# Arduino_DUE_shield_Design.net
KiCad netlist of a schematic drawn in EAGLE
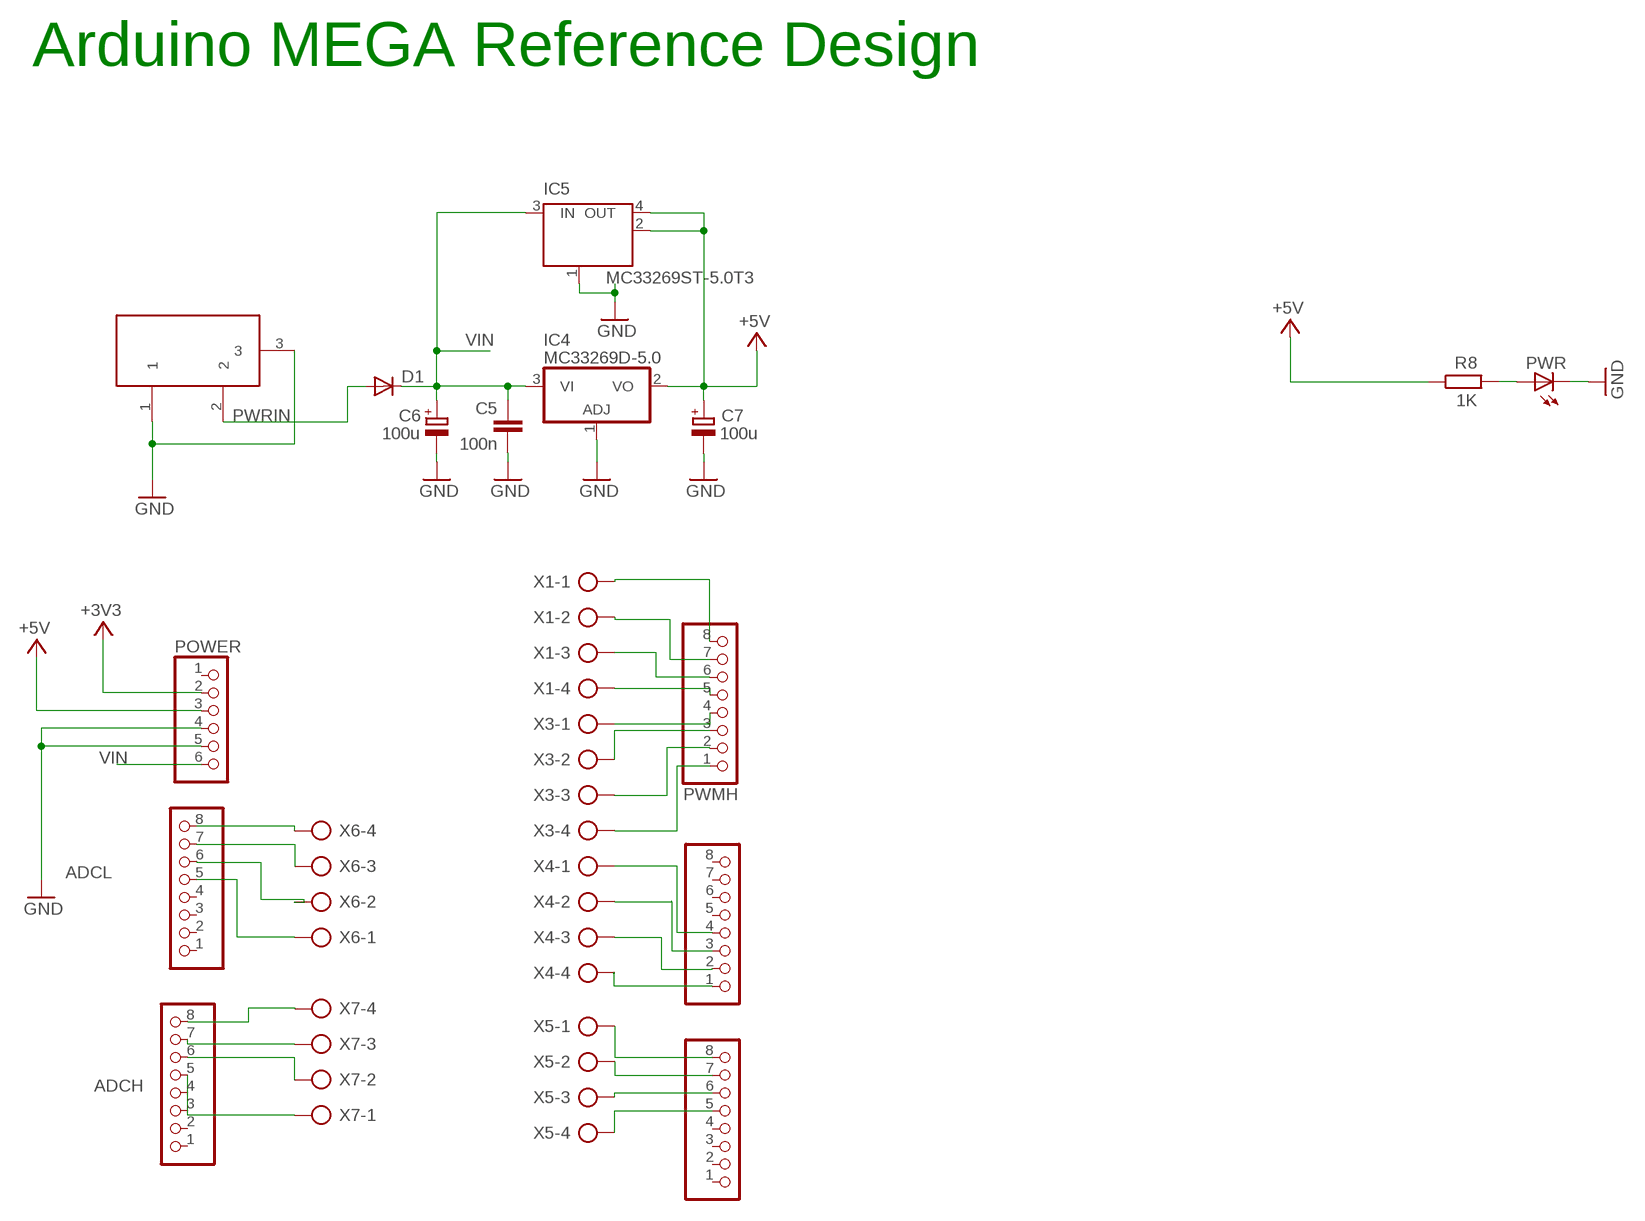
[diagram p0: schematic, sheet 1]

(export (version "E")
  (design (tool "Eeschema 10.0.6"))
  (components
    (comp (ref "ADCH")
      (value "PINHD-1X8")
      (footprint "eagle-import:1X08")
      (libsource (lib "eagle-import") (part "PINHD-1X8"))
    )
    (comp (ref "ADCL")
      (value "PINHD-1X8")
      (footprint "eagle-import:1X08")
      (libsource (lib "eagle-import") (part "PINHD-1X8"))
    )
    (comp (ref "C5")
      (value "100n")
      (footprint "eagle-import:C0805RND")
      (libsource (lib "eagle-import") (part "C-EU"))
    )
    (comp (ref "C6")
      (value "100u")
      (footprint "eagle-import:SMC_D")
      (libsource (lib "eagle-import") (part "CPOL-EUSMCD"))
    )
    (comp (ref "C7")
      (value "100u")
      (footprint "eagle-import:SMC_D")
      (libsource (lib "eagle-import") (part "CPOL-EUSMCD"))
    )
    (comp (ref "COMMUNICATION")
      (value "PINHD-1X8")
      (footprint "eagle-import:1X08")
      (libsource (lib "eagle-import") (part "PINHD-1X8"))
    )
    (comp (ref "D1")
      (value "DIODE-SMB")
      (footprint "eagle-import:SMB")
      (libsource (lib "eagle-import") (part "DIODE-SMB"))
    )
    (comp (ref "IC4")
      (value "MC33269D-5.0")
      (footprint "eagle-import:DPACK")
      (libsource (lib "eagle-import") (part "MC33269?D-5.0"))
    )
    (comp (ref "IC5")
      (value "MC33269ST-5.0T3")
      (footprint "eagle-import:SOT223")
      (libsource (lib "eagle-import") (part "MC33269ST-3.3T3"))
    )
    (comp (ref "POWER")
      (value "PINHD-1X6")
      (footprint "eagle-import:1X06")
      (libsource (lib "eagle-import") (part "PINHD-1X6"))
    )
    (comp (ref "PWMH")
      (value "PINHD-1X8")
      (footprint "eagle-import:1X08")
      (libsource (lib "eagle-import") (part "PINHD-1X8"))
    )
    (comp (ref "PWML")
      (value "PINHD-1X8")
      (footprint "eagle-import:1X08")
      (libsource (lib "eagle-import") (part "PINHD-1X8"))
    )
    (comp (ref "PWR")
      (value "LED0805ROUND")
      (footprint "eagle-import:0805RND")
      (libsource (lib "eagle-import") (part "LED0805ROUND"))
    )
    (comp (ref "R8")
      (value "1K")
      (footprint "eagle-import:R0805RND")
      (libsource (lib "eagle-import") (part "R-EU_"))
    )
    (comp (ref "X1")
      (value "AK500/4")
      (footprint "eagle-import:AK500_4")
      (libsource (lib "eagle-import") (part "AK500/4"))
    )
    (comp (ref "X2")
      (value "DC21MMX")
      (footprint "eagle-import:DC-21MM")
      (libsource (lib "eagle-import") (part "DC21MMX"))
    )
    (comp (ref "X3")
      (value "AK500/4")
      (footprint "eagle-import:AK500_4")
      (libsource (lib "eagle-import") (part "AK500/4"))
    )
    (comp (ref "X4")
      (value "AK500/4")
      (footprint "eagle-import:AK500_4")
      (libsource (lib "eagle-import") (part "AK500/4"))
    )
    (comp (ref "X5")
      (value "AK500/4")
      (footprint "eagle-import:AK500_4")
      (libsource (lib "eagle-import") (part "AK500/4"))
    )
    (comp (ref "X6")
      (value "AK500/4")
      (footprint "eagle-import:AK500_4")
      (libsource (lib "eagle-import") (part "AK500/4"))
    )
    (comp (ref "X7")
      (value "AK500/4")
      (footprint "eagle-import:AK500_4")
      (libsource (lib "eagle-import") (part "AK500/4"))
    )
  )
  (nets
    (net (code "1") (name "+3V3") (class "Default")
      (node (ref "POWER") (pin "2") (pinfunction "2_2") (pintype "passive"))
    )
    (net (code "2") (name "+5V") (class "Default")
      (node (ref "C7") (pin "+") (pinfunction "+_+") (pintype "passive"))
      (node (ref "IC4") (pin "2") (pinfunction "VO_2") (pintype "passive"))
      (node (ref "IC5") (pin "2") (pinfunction "OUT_2") (pintype "passive"))
      (node (ref "IC5") (pin "4") (pinfunction "OUT_4") (pintype "passive"))
      (node (ref "POWER") (pin "3") (pinfunction "3_3") (pintype "passive"))
      (node (ref "R8") (pin "1") (pinfunction "1_1") (pintype "passive"))
    )
    (net (code "3") (name "/PWRIN") (class "Default")
      (node (ref "D1") (pin "A") (pinfunction "A_A") (pintype "passive"))
      (node (ref "X2") (pin "2") (pinfunction "2_2") (pintype "power_in"))
    )
    (net (code "4") (name "/VIN") (class "Default")
      (node (ref "C5") (pin "1") (pinfunction "1_1") (pintype "passive"))
      (node (ref "C6") (pin "+") (pinfunction "+_+") (pintype "passive"))
      (node (ref "D1") (pin "C") (pinfunction "C_C") (pintype "passive"))
      (node (ref "IC4") (pin "3") (pinfunction "VI_3") (pintype "input"))
      (node (ref "IC5") (pin "3") (pinfunction "IN_3") (pintype "input"))
      (node (ref "POWER") (pin "6") (pinfunction "6_6") (pintype "passive"))
    )
    (net (code "5") (name "GND") (class "Default")
      (node (ref "C5") (pin "2") (pinfunction "2_2") (pintype "passive"))
      (node (ref "C6") (pin "-") (pinfunction "-_-") (pintype "passive"))
      (node (ref "C7") (pin "-") (pinfunction "-_-") (pintype "passive"))
      (node (ref "IC4") (pin "1") (pinfunction "ADJ_1") (pintype "input"))
      (node (ref "IC5") (pin "1") (pinfunction "GND/ADJ_1") (pintype "input"))
      (node (ref "POWER") (pin "4") (pinfunction "4_4") (pintype "passive"))
      (node (ref "POWER") (pin "5") (pinfunction "5_5") (pintype "passive"))
      (node (ref "PWR") (pin "P$2") (pinfunction "C_P$2") (pintype "passive"))
      (node (ref "X2") (pin "1") (pinfunction "1_1") (pintype "power_in"))
      (node (ref "X2") (pin "3") (pinfunction "3_3") (pintype "power_in"))
    )
    (net (code "6") (name "Net-(PWR-A)") (class "Default")
      (node (ref "PWR") (pin "P$1") (pinfunction "A_P$1") (pintype "passive"))
      (node (ref "R8") (pin "2") (pinfunction "2_2") (pintype "passive"))
    )
    (net (code "7") (name "Net-(X1A-KL)") (class "Default")
      (node (ref "PWMH") (pin "8") (pinfunction "8_8") (pintype "passive"))
      (node (ref "X1") (pin "1") (pinfunction "KL_1") (pintype "passive"))
    )
    (net (code "8") (name "Net-(X1B-KL)") (class "Default")
      (node (ref "PWMH") (pin "7") (pinfunction "7_7") (pintype "passive"))
      (node (ref "X1") (pin "2") (pinfunction "KL_2") (pintype "passive"))
    )
    (net (code "9") (name "Net-(X1C-KL)") (class "Default")
      (node (ref "PWMH") (pin "6") (pinfunction "6_6") (pintype "passive"))
      (node (ref "X1") (pin "3") (pinfunction "KL_3") (pintype "passive"))
    )
    (net (code "10") (name "Net-(X1D-KL)") (class "Default")
      (node (ref "PWMH") (pin "5") (pinfunction "5_5") (pintype "passive"))
      (node (ref "X1") (pin "4") (pinfunction "KL_4") (pintype "passive"))
    )
    (net (code "11") (name "Net-(X3A-KL)") (class "Default")
      (node (ref "PWMH") (pin "4") (pinfunction "4_4") (pintype "passive"))
      (node (ref "X3") (pin "1") (pinfunction "KL_1") (pintype "passive"))
    )
    (net (code "12") (name "Net-(X3B-KL)") (class "Default")
      (node (ref "PWMH") (pin "3") (pinfunction "3_3") (pintype "passive"))
      (node (ref "X3") (pin "2") (pinfunction "KL_2") (pintype "passive"))
    )
    (net (code "13") (name "Net-(X3C-KL)") (class "Default")
      (node (ref "PWMH") (pin "2") (pinfunction "2_2") (pintype "passive"))
      (node (ref "X3") (pin "3") (pinfunction "KL_3") (pintype "passive"))
    )
    (net (code "14") (name "Net-(X3D-KL)") (class "Default")
      (node (ref "PWMH") (pin "1") (pinfunction "1_1") (pintype "passive"))
      (node (ref "X3") (pin "4") (pinfunction "KL_4") (pintype "passive"))
    )
    (net (code "15") (name "Net-(X4A-KL)") (class "Default")
      (node (ref "PWML") (pin "4") (pinfunction "4_4") (pintype "passive"))
      (node (ref "X4") (pin "1") (pinfunction "KL_1") (pintype "passive"))
    )
    (net (code "16") (name "Net-(X4B-KL)") (class "Default")
      (node (ref "PWML") (pin "3") (pinfunction "3_3") (pintype "passive"))
      (node (ref "X4") (pin "2") (pinfunction "KL_2") (pintype "passive"))
    )
    (net (code "17") (name "Net-(X4C-KL)") (class "Default")
      (node (ref "PWML") (pin "2") (pinfunction "2_2") (pintype "passive"))
      (node (ref "X4") (pin "3") (pinfunction "KL_3") (pintype "passive"))
    )
    (net (code "18") (name "Net-(X4D-KL)") (class "Default")
      (node (ref "PWML") (pin "1") (pinfunction "1_1") (pintype "passive"))
      (node (ref "X4") (pin "4") (pinfunction "KL_4") (pintype "passive"))
    )
    (net (code "19") (name "Net-(X5A-KL)") (class "Default")
      (node (ref "COMMUNICATION") (pin "8") (pinfunction "8_8") (pintype "passive"))
      (node (ref "X5") (pin "1") (pinfunction "KL_1") (pintype "passive"))
    )
    (net (code "20") (name "Net-(X5B-KL)") (class "Default")
      (node (ref "COMMUNICATION") (pin "7") (pinfunction "7_7") (pintype "passive"))
      (node (ref "X5") (pin "2") (pinfunction "KL_2") (pintype "passive"))
    )
    (net (code "21") (name "Net-(X5C-KL)") (class "Default")
      (node (ref "COMMUNICATION") (pin "6") (pinfunction "6_6") (pintype "passive"))
      (node (ref "X5") (pin "3") (pinfunction "KL_3") (pintype "passive"))
    )
    (net (code "22") (name "Net-(X5D-KL)") (class "Default")
      (node (ref "COMMUNICATION") (pin "5") (pinfunction "5_5") (pintype "passive"))
      (node (ref "X5") (pin "4") (pinfunction "KL_4") (pintype "passive"))
    )
    (net (code "23") (name "Net-(X6A-KL)") (class "Default")
      (node (ref "ADCL") (pin "5") (pinfunction "5_5") (pintype "passive"))
      (node (ref "X6") (pin "1") (pinfunction "KL_1") (pintype "passive"))
    )
    (net (code "24") (name "Net-(X6B-KL)") (class "Default")
      (node (ref "ADCL") (pin "6") (pinfunction "6_6") (pintype "passive"))
      (node (ref "X6") (pin "2") (pinfunction "KL_2") (pintype "passive"))
    )
    (net (code "25") (name "Net-(X6C-KL)") (class "Default")
      (node (ref "ADCL") (pin "7") (pinfunction "7_7") (pintype "passive"))
      (node (ref "X6") (pin "3") (pinfunction "KL_3") (pintype "passive"))
    )
    (net (code "26") (name "Net-(X6D-KL)") (class "Default")
      (node (ref "ADCL") (pin "8") (pinfunction "8_8") (pintype "passive"))
      (node (ref "X6") (pin "4") (pinfunction "KL_4") (pintype "passive"))
    )
    (net (code "27") (name "Net-(X7A-KL)") (class "Default")
      (node (ref "ADCH") (pin "5") (pinfunction "5_5") (pintype "passive"))
      (node (ref "X7") (pin "1") (pinfunction "KL_1") (pintype "passive"))
    )
    (net (code "28") (name "Net-(X7B-KL)") (class "Default")
      (node (ref "ADCH") (pin "6") (pinfunction "6_6") (pintype "passive"))
      (node (ref "X7") (pin "2") (pinfunction "KL_2") (pintype "passive"))
    )
    (net (code "29") (name "Net-(X7C-KL)") (class "Default")
      (node (ref "ADCH") (pin "7") (pinfunction "7_7") (pintype "passive"))
      (node (ref "X7") (pin "3") (pinfunction "KL_3") (pintype "passive"))
    )
    (net (code "30") (name "Net-(X7D-KL)") (class "Default")
      (node (ref "ADCH") (pin "8") (pinfunction "8_8") (pintype "passive"))
      (node (ref "X7") (pin "4") (pinfunction "KL_4") (pintype "passive"))
    )
    (net (code "31") (name "unconnected-(ADCH-Pad1)") (class "Default")
      (node (ref "ADCH") (pin "1") (pinfunction "1_1") (pintype "passive"))
    )
    (net (code "32") (name "unconnected-(ADCH-Pad2)") (class "Default")
      (node (ref "ADCH") (pin "2") (pinfunction "2_2") (pintype "passive"))
    )
    (net (code "33") (name "unconnected-(ADCH-Pad3)") (class "Default")
      (node (ref "ADCH") (pin "3") (pinfunction "3_3") (pintype "passive"))
    )
    (net (code "34") (name "unconnected-(ADCH-Pad4)") (class "Default")
      (node (ref "ADCH") (pin "4") (pinfunction "4_4") (pintype "passive"))
    )
    (net (code "35") (name "unconnected-(ADCL-Pad1)") (class "Default")
      (node (ref "ADCL") (pin "1") (pinfunction "1_1") (pintype "passive"))
    )
    (net (code "36") (name "unconnected-(ADCL-Pad2)") (class "Default")
      (node (ref "ADCL") (pin "2") (pinfunction "2_2") (pintype "passive"))
    )
    (net (code "37") (name "unconnected-(ADCL-Pad3)") (class "Default")
      (node (ref "ADCL") (pin "3") (pinfunction "3_3") (pintype "passive"))
    )
    (net (code "38") (name "unconnected-(ADCL-Pad4)") (class "Default")
      (node (ref "ADCL") (pin "4") (pinfunction "4_4") (pintype "passive"))
    )
    (net (code "39") (name "unconnected-(COMMUNICATION-Pad1)") (class "Default")
      (node (ref "COMMUNICATION") (pin "1") (pinfunction "1_1") (pintype "passive"))
    )
    (net (code "40") (name "unconnected-(COMMUNICATION-Pad2)") (class "Default")
      (node (ref "COMMUNICATION") (pin "2") (pinfunction "2_2") (pintype "passive"))
    )
    (net (code "41") (name "unconnected-(COMMUNICATION-Pad3)") (class "Default")
      (node (ref "COMMUNICATION") (pin "3") (pinfunction "3_3") (pintype "passive"))
    )
    (net (code "42") (name "unconnected-(COMMUNICATION-Pad4)") (class "Default")
      (node (ref "COMMUNICATION") (pin "4") (pinfunction "4_4") (pintype "passive"))
    )
    (net (code "43") (name "unconnected-(POWER-Pad1)") (class "Default")
      (node (ref "POWER") (pin "1") (pinfunction "1_1") (pintype "passive"))
    )
    (net (code "44") (name "unconnected-(PWML-Pad5)") (class "Default")
      (node (ref "PWML") (pin "5") (pinfunction "5_5") (pintype "passive"))
    )
    (net (code "45") (name "unconnected-(PWML-Pad6)") (class "Default")
      (node (ref "PWML") (pin "6") (pinfunction "6_6") (pintype "passive"))
    )
    (net (code "46") (name "unconnected-(PWML-Pad7)") (class "Default")
      (node (ref "PWML") (pin "7") (pinfunction "7_7") (pintype "passive"))
    )
    (net (code "47") (name "unconnected-(PWML-Pad8)") (class "Default")
      (node (ref "PWML") (pin "8") (pinfunction "8_8") (pintype "passive"))
    )
  )
)
